# CBUS_Pico_TH_adapter_rev_A.net
KiCad netlist of a schematic drawn in EAGLE
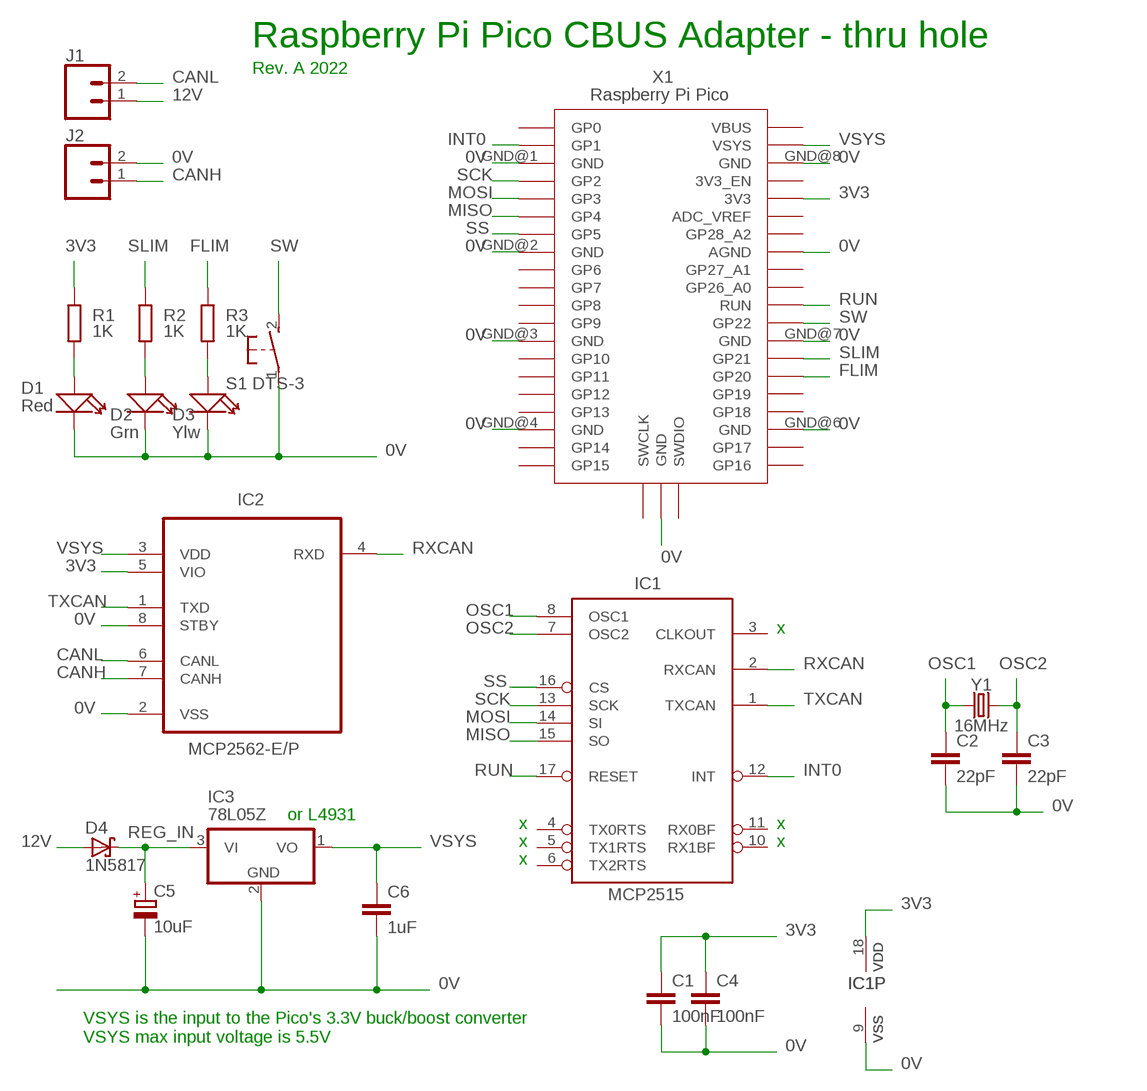
[diagram p0: schematic, sheet 1]

(export (version "E")
  (design (tool "Eeschema 10.0.6"))
  (components
    (comp (ref "C1")
      (value "100nF")
      (footprint "eagle-import:C025-025X050")
      (libsource (lib "eagle-import") (part "C-EU025-025X050"))
    )
    (comp (ref "C2")
      (value "22pF")
      (footprint "eagle-import:C025-025X050")
      (libsource (lib "eagle-import") (part "C-EU025-025X050"))
    )
    (comp (ref "C3")
      (value "22pF")
      (footprint "eagle-import:C025-025X050")
      (libsource (lib "eagle-import") (part "C-EU025-025X050"))
    )
    (comp (ref "C4")
      (value "100nF")
      (footprint "eagle-import:C025-025X050")
      (libsource (lib "eagle-import") (part "C-EU025-025X050"))
    )
    (comp (ref "C5")
      (value "10uF")
      (footprint "eagle-import:E2-4")
      (libsource (lib "eagle-import") (part "CPOL-EUE2-4"))
    )
    (comp (ref "C6")
      (value "1uF")
      (footprint "eagle-import:C025-025X050")
      (libsource (lib "eagle-import") (part "C-EU025-025X050"))
    )
    (comp (ref "D1")
      (value "Red")
      (footprint "eagle-import:LED2-2.54-D3.0MM")
      (fields (field (name "MPN") "SR302DC"))
      (libsource (lib "eagle-import") (part "DIP-LED-RED-RED(2P-D3MM)"))
    )
    (comp (ref "D2")
      (value "Grn")
      (footprint "eagle-import:LED2-2.54-D3.0MM")
      (fields (field (name "MPN") "SR302DC"))
      (libsource (lib "eagle-import") (part "DIP-LED-RED-RED(2P-D3MM)"))
    )
    (comp (ref "D3")
      (value "Ylw")
      (footprint "eagle-import:LED2-2.54-D3.0MM")
      (fields (field (name "MPN") "SR302DC"))
      (libsource (lib "eagle-import") (part "DIP-LED-RED-RED(2P-D3MM)"))
    )
    (comp (ref "D4")
      (value "1N5817")
      (footprint "eagle-import:DO41-10")
      (libsource (lib "eagle-import") (part "SCHOTTKY-DIODEDO41"))
    )
    (comp (ref "IC1")
      (value "MCP2515")
      (footprint "eagle-import:DIP18")
      (libsource (lib "eagle-import") (part "MCP2515(MCP2510)P"))
    )
    (comp (ref "IC2")
      (value "MCP2562-E/P")
      (footprint "eagle-import:DIP254P762X533-8")
      (fields (field (name "MPN") "MCP2562-E/P "))
      (libsource (lib "eagle-import") (part "MCP2562-E/P"))
    )
    (comp (ref "IC3")
      (value "78L05Z")
      (footprint "eagle-import:TO92")
      (libsource (lib "eagle-import") (part "78ZL05"))
    )
    (comp (ref "J1")
      (value "CONN_023.5MM")
      (footprint "eagle-import:SCREWTERMINAL-3.5MM-2")
      (libsource (lib "eagle-import") (part "CONN_023.5MM"))
    )
    (comp (ref "J2")
      (value "CONN_023.5MM")
      (footprint "eagle-import:SCREWTERMINAL-3.5MM-2")
      (libsource (lib "eagle-import") (part "CONN_023.5MM"))
    )
    (comp (ref "R1")
      (value "1K")
      (footprint "eagle-import:0207_10")
      (libsource (lib "eagle-import") (part "R-EU_0207/10"))
    )
    (comp (ref "R2")
      (value "1K")
      (footprint "eagle-import:0207_10")
      (libsource (lib "eagle-import") (part "R-EU_0207/10"))
    )
    (comp (ref "R3")
      (value "1K")
      (footprint "eagle-import:0207_10")
      (libsource (lib "eagle-import") (part "R-EU_0207/10"))
    )
    (comp (ref "S1")
      (value "DTS-3")
      (footprint "eagle-import:DTS-3")
      (libsource (lib "eagle-import") (part "DTS-3"))
    )
    (comp (ref "X1")
      (value "Raspberry Pi Pico")
      (footprint "eagle-import:RPI_PICO_TH")
      (libsource (lib "eagle-import") (part "RPI_PICO_IG-TH"))
    )
    (comp (ref "Y1")
      (value "16MHz")
      (footprint "eagle-import:HC49US")
      (libsource (lib "eagle-import") (part "CRYSTAL-16MHZPTH-HC49US"))
    )
  )
  (nets
    (net (code "1") (name "/0V") (class "Default")
      (node (ref "C1") (pin "2") (pinfunction "2_2") (pintype "passive"))
      (node (ref "C2") (pin "2") (pinfunction "2_2") (pintype "passive"))
      (node (ref "C3") (pin "2") (pinfunction "2_2") (pintype "passive"))
      (node (ref "C4") (pin "2") (pinfunction "2_2") (pintype "passive"))
      (node (ref "C5") (pin "-") (pinfunction "-_-") (pintype "passive"))
      (node (ref "C6") (pin "2") (pinfunction "2_2") (pintype "passive"))
      (node (ref "D1") (pin "K") (pinfunction "-_K") (pintype "passive"))
      (node (ref "D2") (pin "K") (pinfunction "-_K") (pintype "passive"))
      (node (ref "D3") (pin "K") (pinfunction "-_K") (pintype "passive"))
      (node (ref "IC1") (pin "9") (pinfunction "VSS_9") (pintype "power_in"))
      (node (ref "IC2") (pin "2") (pinfunction "VSS_2") (pintype "power_in"))
      (node (ref "IC2") (pin "8") (pinfunction "STBY_8") (pintype "input"))
      (node (ref "IC3") (pin "2") (pinfunction "GND_2") (pintype "passive"))
      (node (ref "J2") (pin "2") (pinfunction "2_2") (pintype "passive"))
      (node (ref "S1") (pin "1") (pinfunction "1_1") (pintype "passive"))
      (node (ref "X1") (pin "AGND") (pinfunction "AGND_AGND") (pintype "bidirectional"))
      (node (ref "X1") (pin "GND@1") (pinfunction "GND_GND@1") (pintype "bidirectional"))
      (node (ref "X1") (pin "GND@2") (pinfunction "GND_GND@2") (pintype "bidirectional"))
      (node (ref "X1") (pin "GND@3") (pinfunction "GND_GND@3") (pintype "bidirectional"))
      (node (ref "X1") (pin "GND@4") (pinfunction "GND_GND@4") (pintype "bidirectional"))
      (node (ref "X1") (pin "GND@5") (pinfunction "GND_GND@5") (pintype "bidirectional"))
      (node (ref "X1") (pin "GND@6") (pinfunction "GND_GND@6") (pintype "bidirectional"))
      (node (ref "X1") (pin "GND@7") (pinfunction "GND_GND@7") (pintype "bidirectional"))
      (node (ref "X1") (pin "GND@8") (pinfunction "GND_GND@8") (pintype "bidirectional"))
    )
    (net (code "2") (name "/3V3") (class "Default")
      (node (ref "C1") (pin "1") (pinfunction "1_1") (pintype "passive"))
      (node (ref "C4") (pin "1") (pinfunction "1_1") (pintype "passive"))
      (node (ref "IC1") (pin "18") (pinfunction "VDD_18") (pintype "power_in"))
      (node (ref "IC2") (pin "5") (pinfunction "VIO_5") (pintype "power_in"))
      (node (ref "R1") (pin "1") (pinfunction "1_1") (pintype "passive"))
      (node (ref "X1") (pin "3V3") (pinfunction "3V3_3V3") (pintype "bidirectional"))
    )
    (net (code "3") (name "/12V") (class "Default")
      (node (ref "D4") (pin "A") (pinfunction "A_A") (pintype "passive"))
      (node (ref "J1") (pin "1") (pinfunction "1_1") (pintype "passive"))
    )
    (net (code "4") (name "/CANH") (class "Default")
      (node (ref "IC2") (pin "7") (pinfunction "CANH_7") (pintype "bidirectional"))
      (node (ref "J2") (pin "1") (pinfunction "1_1") (pintype "passive"))
    )
    (net (code "5") (name "/CANL") (class "Default")
      (node (ref "IC2") (pin "6") (pinfunction "CANL_6") (pintype "bidirectional"))
      (node (ref "J1") (pin "2") (pinfunction "2_2") (pintype "passive"))
    )
    (net (code "6") (name "/FLIM") (class "Default")
      (node (ref "R3") (pin "1") (pinfunction "1_1") (pintype "passive"))
      (node (ref "X1") (pin "GP20") (pinfunction "GP20_GP20") (pintype "bidirectional"))
    )
    (net (code "7") (name "/INT0") (class "Default")
      (node (ref "IC1") (pin "12") (pinfunction "INT_12") (pintype "output"))
      (node (ref "X1") (pin "GP1") (pinfunction "GP1_GP1") (pintype "bidirectional"))
    )
    (net (code "8") (name "/MISO") (class "Default")
      (node (ref "IC1") (pin "15") (pinfunction "SO_15") (pintype "output"))
      (node (ref "X1") (pin "GP4") (pinfunction "GP4_GP4") (pintype "bidirectional"))
    )
    (net (code "9") (name "/MOSI") (class "Default")
      (node (ref "IC1") (pin "14") (pinfunction "SI_14") (pintype "input"))
      (node (ref "X1") (pin "GP3") (pinfunction "GP3_GP3") (pintype "bidirectional"))
    )
    (net (code "10") (name "/OSC1") (class "Default")
      (node (ref "C2") (pin "1") (pinfunction "1_1") (pintype "passive"))
      (node (ref "IC1") (pin "8") (pinfunction "OSC1_8") (pintype "input"))
      (node (ref "Y1") (pin "1") (pinfunction "1_1") (pintype "passive"))
    )
    (net (code "11") (name "/OSC2") (class "Default")
      (node (ref "C3") (pin "1") (pinfunction "1_1") (pintype "passive"))
      (node (ref "IC1") (pin "7") (pinfunction "OSC2_7") (pintype "output"))
      (node (ref "Y1") (pin "2") (pinfunction "2_2") (pintype "passive"))
    )
    (net (code "12") (name "/REG_IN") (class "Default")
      (node (ref "C5") (pin "+") (pinfunction "+_+") (pintype "passive"))
      (node (ref "D4") (pin "C") (pinfunction "C_C") (pintype "passive"))
      (node (ref "IC3") (pin "3") (pinfunction "VI_3") (pintype "input"))
    )
    (net (code "13") (name "/RUN") (class "Default")
      (node (ref "IC1") (pin "17") (pinfunction "RESET_17") (pintype "input"))
      (node (ref "X1") (pin "RUN") (pinfunction "RUN_RUN") (pintype "bidirectional"))
    )
    (net (code "14") (name "/RXCAN") (class "Default")
      (node (ref "IC1") (pin "2") (pinfunction "RXCAN_2") (pintype "input"))
      (node (ref "IC2") (pin "4") (pinfunction "RXD_4") (pintype "output"))
    )
    (net (code "15") (name "/SCK") (class "Default")
      (node (ref "IC1") (pin "13") (pinfunction "SCK_13") (pintype "input"))
      (node (ref "X1") (pin "GP2") (pinfunction "GP2_GP2") (pintype "bidirectional"))
    )
    (net (code "16") (name "/SLIM") (class "Default")
      (node (ref "R2") (pin "1") (pinfunction "1_1") (pintype "passive"))
      (node (ref "X1") (pin "GP21") (pinfunction "GP21_GP21") (pintype "bidirectional"))
    )
    (net (code "17") (name "/SS") (class "Default")
      (node (ref "IC1") (pin "16") (pinfunction "CS_16") (pintype "input"))
      (node (ref "X1") (pin "GP5") (pinfunction "GP5_GP5") (pintype "bidirectional"))
    )
    (net (code "18") (name "/SW") (class "Default")
      (node (ref "S1") (pin "2") (pinfunction "2_2") (pintype "passive"))
      (node (ref "X1") (pin "GP22") (pinfunction "GP22_GP22") (pintype "bidirectional"))
    )
    (net (code "19") (name "/TXCAN") (class "Default")
      (node (ref "IC1") (pin "1") (pinfunction "TXCAN_1") (pintype "output"))
      (node (ref "IC2") (pin "1") (pinfunction "TXD_1") (pintype "input"))
    )
    (net (code "20") (name "/VSYS") (class "Default")
      (node (ref "C6") (pin "1") (pinfunction "1_1") (pintype "passive"))
      (node (ref "IC2") (pin "3") (pinfunction "VDD_3") (pintype "power_in"))
      (node (ref "IC3") (pin "1") (pinfunction "VO_1") (pintype "passive"))
      (node (ref "X1") (pin "VSYS") (pinfunction "VSYS_VSYS") (pintype "bidirectional"))
    )
    (net (code "21") (name "Net-(D1-+)") (class "Default")
      (node (ref "D1") (pin "A") (pinfunction "+_A") (pintype "passive"))
      (node (ref "R1") (pin "2") (pinfunction "2_2") (pintype "passive"))
    )
    (net (code "22") (name "Net-(D2-+)") (class "Default")
      (node (ref "D2") (pin "A") (pinfunction "+_A") (pintype "passive"))
      (node (ref "R2") (pin "2") (pinfunction "2_2") (pintype "passive"))
    )
    (net (code "23") (name "Net-(D3-+)") (class "Default")
      (node (ref "D3") (pin "A") (pinfunction "+_A") (pintype "passive"))
      (node (ref "R3") (pin "2") (pinfunction "2_2") (pintype "passive"))
    )
    (net (code "24") (name "unconnected-(IC1A-CLKOUT-Pad3)") (class "Default")
      (node (ref "IC1") (pin "3") (pinfunction "CLKOUT_3") (pintype "output"))
    )
    (net (code "25") (name "unconnected-(IC1A-RX0BF-Pad11)") (class "Default")
      (node (ref "IC1") (pin "11") (pinfunction "RX0BF_11") (pintype "output"))
    )
    (net (code "26") (name "unconnected-(IC1A-RX1BF-Pad10)") (class "Default")
      (node (ref "IC1") (pin "10") (pinfunction "RX1BF_10") (pintype "output"))
    )
    (net (code "27") (name "unconnected-(IC1A-TX0RTS-Pad4)") (class "Default")
      (node (ref "IC1") (pin "4") (pinfunction "TX0RTS_4") (pintype "input"))
    )
    (net (code "28") (name "unconnected-(IC1A-TX1RTS-Pad5)") (class "Default")
      (node (ref "IC1") (pin "5") (pinfunction "TX1RTS_5") (pintype "input"))
    )
    (net (code "29") (name "unconnected-(IC1A-TX2RTS-Pad6)") (class "Default")
      (node (ref "IC1") (pin "6") (pinfunction "TX2RTS_6") (pintype "input"))
    )
    (net (code "30") (name "unconnected-(X1-Pad3V3_EN)") (class "Default")
      (node (ref "X1") (pin "3V3_EN") (pinfunction "3V3_EN_3V3_EN") (pintype "bidirectional"))
    )
    (net (code "31") (name "unconnected-(X1-PadADC_VREF)") (class "Default")
      (node (ref "X1") (pin "ADC_VREF") (pinfunction "ADC_VREF_ADC_VREF") (pintype "bidirectional"))
    )
    (net (code "32") (name "unconnected-(X1-PadGP0)") (class "Default")
      (node (ref "X1") (pin "GP0") (pinfunction "GP0_GP0") (pintype "bidirectional"))
    )
    (net (code "33") (name "unconnected-(X1-PadGP6)") (class "Default")
      (node (ref "X1") (pin "GP6") (pinfunction "GP6_GP6") (pintype "bidirectional"))
    )
    (net (code "34") (name "unconnected-(X1-PadGP7)") (class "Default")
      (node (ref "X1") (pin "GP7") (pinfunction "GP7_GP7") (pintype "bidirectional"))
    )
    (net (code "35") (name "unconnected-(X1-PadGP8)") (class "Default")
      (node (ref "X1") (pin "GP8") (pinfunction "GP8_GP8") (pintype "bidirectional"))
    )
    (net (code "36") (name "unconnected-(X1-PadGP9)") (class "Default")
      (node (ref "X1") (pin "GP9") (pinfunction "GP9_GP9") (pintype "bidirectional"))
    )
    (net (code "37") (name "unconnected-(X1-PadGP10)") (class "Default")
      (node (ref "X1") (pin "GP10") (pinfunction "GP10_GP10") (pintype "bidirectional"))
    )
    (net (code "38") (name "unconnected-(X1-PadGP11)") (class "Default")
      (node (ref "X1") (pin "GP11") (pinfunction "GP11_GP11") (pintype "bidirectional"))
    )
    (net (code "39") (name "unconnected-(X1-PadGP12)") (class "Default")
      (node (ref "X1") (pin "GP12") (pinfunction "GP12_GP12") (pintype "bidirectional"))
    )
    (net (code "40") (name "unconnected-(X1-PadGP13)") (class "Default")
      (node (ref "X1") (pin "GP13") (pinfunction "GP13_GP13") (pintype "bidirectional"))
    )
    (net (code "41") (name "unconnected-(X1-PadGP14)") (class "Default")
      (node (ref "X1") (pin "GP14") (pinfunction "GP14_GP14") (pintype "bidirectional"))
    )
    (net (code "42") (name "unconnected-(X1-PadGP15)") (class "Default")
      (node (ref "X1") (pin "GP15") (pinfunction "GP15_GP15") (pintype "bidirectional"))
    )
    (net (code "43") (name "unconnected-(X1-PadGP16)") (class "Default")
      (node (ref "X1") (pin "GP16") (pinfunction "GP16_GP16") (pintype "bidirectional"))
    )
    (net (code "44") (name "unconnected-(X1-PadGP17)") (class "Default")
      (node (ref "X1") (pin "GP17") (pinfunction "GP17_GP17") (pintype "bidirectional"))
    )
    (net (code "45") (name "unconnected-(X1-PadGP18)") (class "Default")
      (node (ref "X1") (pin "GP18") (pinfunction "GP18_GP18") (pintype "bidirectional"))
    )
    (net (code "46") (name "unconnected-(X1-PadGP19)") (class "Default")
      (node (ref "X1") (pin "GP19") (pinfunction "GP19_GP19") (pintype "bidirectional"))
    )
    (net (code "47") (name "unconnected-(X1-PadGP26_A0)") (class "Default")
      (node (ref "X1") (pin "GP26_A0") (pinfunction "GP26_A0_GP26_A0") (pintype "bidirectional"))
    )
    (net (code "48") (name "unconnected-(X1-PadGP27_A1)") (class "Default")
      (node (ref "X1") (pin "GP27_A1") (pinfunction "GP27_A1_GP27_A1") (pintype "bidirectional"))
    )
    (net (code "49") (name "unconnected-(X1-PadGP28_A2)") (class "Default")
      (node (ref "X1") (pin "GP28_A2") (pinfunction "GP28_A2_GP28_A2") (pintype "bidirectional"))
    )
    (net (code "50") (name "unconnected-(X1-PadSWCLK)") (class "Default")
      (node (ref "X1") (pin "SWCLK") (pinfunction "SWCLK_SWCLK") (pintype "bidirectional"))
    )
    (net (code "51") (name "unconnected-(X1-PadSWDIO)") (class "Default")
      (node (ref "X1") (pin "SWDIO") (pinfunction "SWDIO_SWDIO") (pintype "bidirectional"))
    )
    (net (code "52") (name "unconnected-(X1-PadVBUS)") (class "Default")
      (node (ref "X1") (pin "VBUS") (pinfunction "VBUS_VBUS") (pintype "bidirectional"))
    )
  )
)
